# PineWoodDerby_Mega_Shield.net
KiCad netlist of a schematic drawn in EAGLE
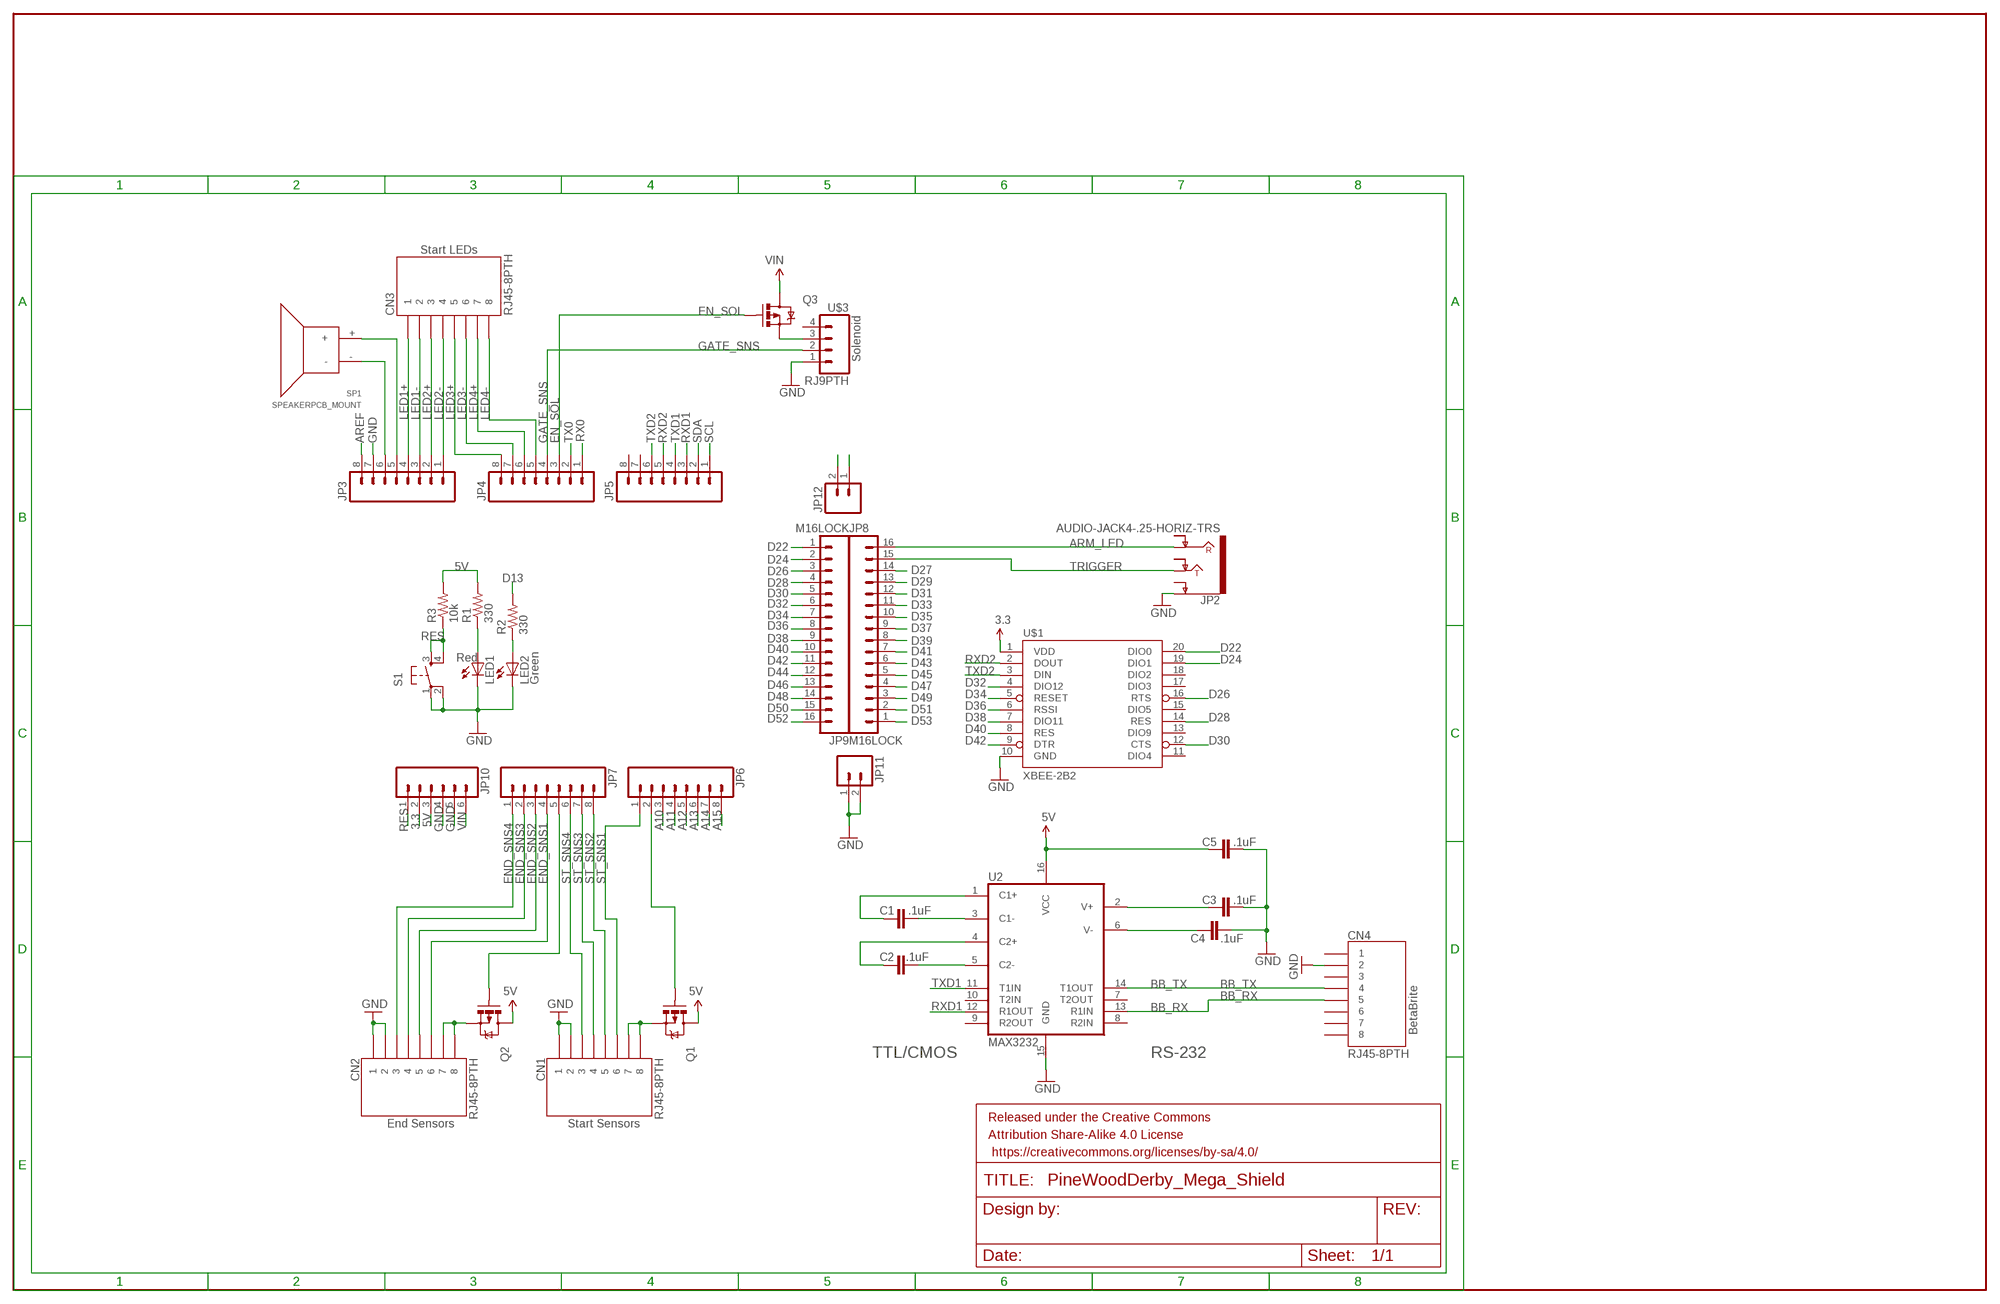
[diagram p0: schematic, sheet 1]

(export (version "E")
  (design (tool "Eeschema 10.0.6"))
  (components
    (comp (ref "C1")
      (value ".1uF")
      (footprint "eagle-import:0402-CAP")
      (libsource (lib "eagle-import") (part "CAP0402-CAP"))
    )
    (comp (ref "C2")
      (value ".1uF")
      (footprint "eagle-import:0402-CAP")
      (libsource (lib "eagle-import") (part "CAP0402-CAP"))
    )
    (comp (ref "C3")
      (value ".1uF")
      (footprint "eagle-import:0402-CAP")
      (libsource (lib "eagle-import") (part "CAP0402-CAP"))
    )
    (comp (ref "C4")
      (value ".1uF")
      (footprint "eagle-import:0402-CAP")
      (libsource (lib "eagle-import") (part "CAP0402-CAP"))
    )
    (comp (ref "C5")
      (value ".1uF")
      (footprint "eagle-import:0402-CAP")
      (libsource (lib "eagle-import") (part "CAP0402-CAP"))
    )
    (comp (ref "CN1")
      (value "RJ45-8PTH")
      (footprint "eagle-import:RJ45-8")
      (fields (field (name "LABEL") "Start Sensors"))
      (libsource (lib "eagle-import") (part "RJ45-8PTH"))
    )
    (comp (ref "CN2")
      (value "RJ45-8PTH")
      (footprint "eagle-import:RJ45-8")
      (fields (field (name "LABEL") "End Sensors"))
      (libsource (lib "eagle-import") (part "RJ45-8PTH"))
    )
    (comp (ref "CN3")
      (value "RJ45-8PTH")
      (footprint "eagle-import:RJ45-8")
      (fields (field (name "LABEL") "Start LEDs"))
      (libsource (lib "eagle-import") (part "RJ45-8PTH"))
    )
    (comp (ref "CN4")
      (value "RJ45-8PTH")
      (footprint "eagle-import:RJ45-8")
      (fields (field (name "LABEL") "BetaBrite"))
      (libsource (lib "eagle-import") (part "RJ45-8PTH"))
    )
    (comp (ref "FRAME2")
      (value "FRAME-LEDGER")
      (footprint "eagle-import:CREATIVE_COMMONS")
      (libsource (lib "eagle-import") (part "FRAME-LEDGER"))
    )
    (comp (ref "JP2")
      (value "AUDIO-JACK4-.25-HORIZ-TRS")
      (footprint "eagle-import:AUDIO-JACK-.25-INCH-HORIZ-PTH")
      (libsource (lib "eagle-import") (part "AUDIO-JACK4-.25-HORIZ-TRS"))
    )
    (comp (ref "JP3")
      (value "M08LOCK")
      (footprint "eagle-import:1X08_LOCK")
      (libsource (lib "eagle-import") (part "M08LOCK"))
    )
    (comp (ref "JP4")
      (value "M08LOCK")
      (footprint "eagle-import:1X08_LOCK")
      (libsource (lib "eagle-import") (part "M08LOCK"))
    )
    (comp (ref "JP5")
      (value "M08LOCK")
      (footprint "eagle-import:1X08_LOCK")
      (libsource (lib "eagle-import") (part "M08LOCK"))
    )
    (comp (ref "JP6")
      (value "M08LOCK")
      (footprint "eagle-import:1X08_LOCK")
      (libsource (lib "eagle-import") (part "M08LOCK"))
    )
    (comp (ref "JP7")
      (value "M08LOCK")
      (footprint "eagle-import:1X08_LOCK")
      (libsource (lib "eagle-import") (part "M08LOCK"))
    )
    (comp (ref "JP8")
      (value "M16LOCK")
      (footprint "eagle-import:1X16_LOCK")
      (libsource (lib "eagle-import") (part "M16LOCK"))
    )
    (comp (ref "JP9")
      (value "M16LOCK")
      (footprint "eagle-import:1X16_LOCK")
      (libsource (lib "eagle-import") (part "M16LOCK"))
    )
    (comp (ref "JP10")
      (value "M06LOCK")
      (footprint "eagle-import:1X06_LOCK")
      (libsource (lib "eagle-import") (part "M06LOCK"))
    )
    (comp (ref "JP11")
      (value "M02LOCK")
      (footprint "eagle-import:1X02_LOCK")
      (libsource (lib "eagle-import") (part "M02LOCK"))
    )
    (comp (ref "JP12")
      (value "M02LOCK")
      (footprint "eagle-import:1X02_LOCK")
      (libsource (lib "eagle-import") (part "M02LOCK"))
    )
    (comp (ref "LED1")
      (value "Red")
      (footprint "eagle-import:LED5MM")
      (libsource (lib "eagle-import") (part "LED5MM"))
    )
    (comp (ref "LED2")
      (value "Green")
      (footprint "eagle-import:LED5MM")
      (libsource (lib "eagle-import") (part "LED5MM"))
    )
    (comp (ref "Q1")
      (value "MOSFET-PCHANNELFQP27P06")
      (footprint "eagle-import:TO220V")
      (libsource (lib "eagle-import") (part "MOSFET-PCHANNELFQP27P06"))
    )
    (comp (ref "Q2")
      (value "MOSFET-PCHANNELFQP27P06")
      (footprint "eagle-import:TO220V")
      (libsource (lib "eagle-import") (part "MOSFET-PCHANNELFQP27P06"))
    )
    (comp (ref "Q3")
      (value "MOSFET-PCHANNELFQP27P06")
      (footprint "eagle-import:TO220V")
      (libsource (lib "eagle-import") (part "MOSFET-PCHANNELFQP27P06"))
    )
    (comp (ref "R1")
      (value "330")
      (footprint "eagle-import:AXIAL-0.3")
      (libsource (lib "eagle-import") (part "RESISTORPTH1"))
    )
    (comp (ref "R2")
      (value "330")
      (footprint "eagle-import:AXIAL-0.3")
      (libsource (lib "eagle-import") (part "RESISTORPTH1"))
    )
    (comp (ref "R3")
      (value "10k")
      (footprint "eagle-import:AXIAL-0.3")
      (libsource (lib "eagle-import") (part "RESISTORPTH1"))
    )
    (comp (ref "S1")
      (value "TAC_SWITCHPTH")
      (footprint "eagle-import:TACTILE-PTH")
      (libsource (lib "eagle-import") (part "TAC_SWITCHPTH"))
    )
    (comp (ref "SP1")
      (value "SPEAKERPCB_MOUNT")
      (footprint "eagle-import:PCB_MOUNT_SPEAKER")
      (fields (field (name "MFG") "SANCO"))
      (libsource (lib "eagle-import") (part "SPEAKERPCB_MOUNT"))
    )
    (comp (ref "U$1")
      (value "XBEE-2B2")
      (footprint "eagle-import:XBEE-SILK")
      (libsource (lib "eagle-import") (part "XBEE-2B2"))
    )
    (comp (ref "U$3")
      (value "RJ9PTH")
      (footprint "eagle-import:RJ9")
      (fields (field (name "LABEL") "Solenoid"))
      (libsource (lib "eagle-import") (part "RJ9PTH"))
    )
    (comp (ref "U2")
      (value "MAX3232")
      (footprint "eagle-import:SO016")
      (fields (field (name "PROD_ID") "IC-08171"))
      (libsource (lib "eagle-import") (part "MAX232SOIC16"))
    )
  )
  (nets
    (net (code "1") (name "/5V@1") (class "Default")
      (node (ref "JP12") (pin "1") (pinfunction "1_1") (pintype "passive"))
      (node (ref "JP12") (pin "2") (pinfunction "2_2") (pintype "passive"))
    )
    (net (code "2") (name "/A10") (class "Default")
      (node (ref "JP6") (pin "3") (pinfunction "3_3") (pintype "passive"))
    )
    (net (code "3") (name "/A11") (class "Default")
      (node (ref "JP6") (pin "4") (pinfunction "4_4") (pintype "passive"))
    )
    (net (code "4") (name "/A12") (class "Default")
      (node (ref "JP6") (pin "5") (pinfunction "5_5") (pintype "passive"))
    )
    (net (code "5") (name "/A13") (class "Default")
      (node (ref "JP6") (pin "6") (pinfunction "6_6") (pintype "passive"))
    )
    (net (code "6") (name "/A14") (class "Default")
      (node (ref "JP6") (pin "7") (pinfunction "7_7") (pintype "passive"))
    )
    (net (code "7") (name "/A15") (class "Default")
      (node (ref "JP6") (pin "8") (pinfunction "8_8") (pintype "passive"))
    )
    (net (code "8") (name "/AREF") (class "Default")
      (node (ref "JP3") (pin "8") (pinfunction "8_8") (pintype "passive"))
    )
    (net (code "9") (name "/ARM_LED") (class "Default")
      (node (ref "JP2") (pin "RING") (pinfunction "RING_RING") (pintype "bidirectional"))
      (node (ref "JP8") (pin "16") (pinfunction "16_16") (pintype "passive"))
    )
    (net (code "10") (name "/BB_RX") (class "Default")
      (node (ref "CN4") (pin "5") (pinfunction "5_5") (pintype "bidirectional"))
      (node (ref "U2") (pin "13") (pinfunction "R1IN_13") (pintype "input"))
    )
    (net (code "11") (name "/BB_TX") (class "Default")
      (node (ref "CN4") (pin "4") (pinfunction "4_4") (pintype "bidirectional"))
      (node (ref "U2") (pin "14") (pinfunction "T1OUT_14") (pintype "output"))
    )
    (net (code "12") (name "/D13") (class "Default")
      (node (ref "R2") (pin "P$2") (pinfunction "2_P$2") (pintype "passive"))
    )
    (net (code "13") (name "/D22") (class "Default")
      (node (ref "JP9") (pin "1") (pinfunction "1_1") (pintype "passive"))
      (node (ref "U$1") (pin "20") (pinfunction "DIO0_20") (pintype "bidirectional"))
    )
    (net (code "14") (name "/D24") (class "Default")
      (node (ref "JP9") (pin "2") (pinfunction "2_2") (pintype "passive"))
      (node (ref "U$1") (pin "19") (pinfunction "DIO1_19") (pintype "bidirectional"))
    )
    (net (code "15") (name "/D26") (class "Default")
      (node (ref "JP9") (pin "3") (pinfunction "3_3") (pintype "passive"))
      (node (ref "U$1") (pin "16") (pinfunction "RTS_16") (pintype "input"))
    )
    (net (code "16") (name "/D27") (class "Default")
      (node (ref "JP8") (pin "14") (pinfunction "14_14") (pintype "passive"))
    )
    (net (code "17") (name "/D28") (class "Default")
      (node (ref "JP9") (pin "4") (pinfunction "4_4") (pintype "passive"))
      (node (ref "U$1") (pin "14") (pinfunction "RES_14") (pintype "bidirectional"))
    )
    (net (code "18") (name "/D29") (class "Default")
      (node (ref "JP8") (pin "13") (pinfunction "13_13") (pintype "passive"))
    )
    (net (code "19") (name "/D30") (class "Default")
      (node (ref "JP9") (pin "5") (pinfunction "5_5") (pintype "passive"))
      (node (ref "U$1") (pin "12") (pinfunction "CTS_12") (pintype "output"))
    )
    (net (code "20") (name "/D31") (class "Default")
      (node (ref "JP8") (pin "12") (pinfunction "12_12") (pintype "passive"))
    )
    (net (code "21") (name "/D32") (class "Default")
      (node (ref "JP9") (pin "6") (pinfunction "6_6") (pintype "passive"))
      (node (ref "U$1") (pin "4") (pinfunction "DIO12_4") (pintype "bidirectional"))
    )
    (net (code "22") (name "/D33") (class "Default")
      (node (ref "JP8") (pin "11") (pinfunction "11_11") (pintype "passive"))
    )
    (net (code "23") (name "/D34") (class "Default")
      (node (ref "JP9") (pin "7") (pinfunction "7_7") (pintype "passive"))
      (node (ref "U$1") (pin "5") (pinfunction "RESET_5") (pintype "input"))
    )
    (net (code "24") (name "/D35") (class "Default")
      (node (ref "JP8") (pin "10") (pinfunction "10_10") (pintype "passive"))
    )
    (net (code "25") (name "/D36") (class "Default")
      (node (ref "JP9") (pin "8") (pinfunction "8_8") (pintype "passive"))
      (node (ref "U$1") (pin "6") (pinfunction "RSSI_6") (pintype "bidirectional"))
    )
    (net (code "26") (name "/D37") (class "Default")
      (node (ref "JP8") (pin "9") (pinfunction "9_9") (pintype "passive"))
    )
    (net (code "27") (name "/D38") (class "Default")
      (node (ref "JP9") (pin "9") (pinfunction "9_9") (pintype "passive"))
      (node (ref "U$1") (pin "7") (pinfunction "DIO11_7") (pintype "bidirectional"))
    )
    (net (code "28") (name "/D39") (class "Default")
      (node (ref "JP8") (pin "8") (pinfunction "8_8") (pintype "passive"))
    )
    (net (code "29") (name "/D40") (class "Default")
      (node (ref "JP9") (pin "10") (pinfunction "10_10") (pintype "passive"))
      (node (ref "U$1") (pin "8") (pinfunction "RES_8") (pintype "bidirectional"))
    )
    (net (code "30") (name "/D41") (class "Default")
      (node (ref "JP8") (pin "7") (pinfunction "7_7") (pintype "passive"))
    )
    (net (code "31") (name "/D42") (class "Default")
      (node (ref "JP9") (pin "11") (pinfunction "11_11") (pintype "passive"))
      (node (ref "U$1") (pin "9") (pinfunction "DTR_9") (pintype "bidirectional"))
    )
    (net (code "32") (name "/D43") (class "Default")
      (node (ref "JP8") (pin "6") (pinfunction "6_6") (pintype "passive"))
    )
    (net (code "33") (name "/D44") (class "Default")
      (node (ref "JP9") (pin "12") (pinfunction "12_12") (pintype "passive"))
    )
    (net (code "34") (name "/D45") (class "Default")
      (node (ref "JP8") (pin "5") (pinfunction "5_5") (pintype "passive"))
    )
    (net (code "35") (name "/D46") (class "Default")
      (node (ref "JP9") (pin "13") (pinfunction "13_13") (pintype "passive"))
    )
    (net (code "36") (name "/D47") (class "Default")
      (node (ref "JP8") (pin "4") (pinfunction "4_4") (pintype "passive"))
    )
    (net (code "37") (name "/D48") (class "Default")
      (node (ref "JP9") (pin "14") (pinfunction "14_14") (pintype "passive"))
    )
    (net (code "38") (name "/D49") (class "Default")
      (node (ref "JP8") (pin "3") (pinfunction "3_3") (pintype "passive"))
    )
    (net (code "39") (name "/D50") (class "Default")
      (node (ref "JP9") (pin "15") (pinfunction "15_15") (pintype "passive"))
    )
    (net (code "40") (name "/D51") (class "Default")
      (node (ref "JP8") (pin "2") (pinfunction "2_2") (pintype "passive"))
    )
    (net (code "41") (name "/D52") (class "Default")
      (node (ref "JP9") (pin "16") (pinfunction "16_16") (pintype "passive"))
    )
    (net (code "42") (name "/D53") (class "Default")
      (node (ref "JP8") (pin "1") (pinfunction "1_1") (pintype "passive"))
    )
    (net (code "43") (name "/END_SNS1") (class "Default")
      (node (ref "CN2") (pin "6") (pinfunction "6_6") (pintype "bidirectional"))
      (node (ref "JP7") (pin "4") (pinfunction "4_4") (pintype "passive"))
    )
    (net (code "44") (name "/END_SNS2") (class "Default")
      (node (ref "CN2") (pin "5") (pinfunction "5_5") (pintype "bidirectional"))
      (node (ref "JP7") (pin "3") (pinfunction "3_3") (pintype "passive"))
    )
    (net (code "45") (name "/END_SNS3") (class "Default")
      (node (ref "CN2") (pin "4") (pinfunction "4_4") (pintype "bidirectional"))
      (node (ref "JP7") (pin "2") (pinfunction "2_2") (pintype "passive"))
    )
    (net (code "46") (name "/END_SNS4") (class "Default")
      (node (ref "CN2") (pin "3") (pinfunction "3_3") (pintype "bidirectional"))
      (node (ref "JP7") (pin "1") (pinfunction "1_1") (pintype "passive"))
    )
    (net (code "47") (name "/EN_SOL") (class "Default")
      (node (ref "JP4") (pin "3") (pinfunction "3_3") (pintype "passive"))
      (node (ref "Q3") (pin "1") (pinfunction "G_1") (pintype "passive"))
    )
    (net (code "48") (name "/GATE_SNS") (class "Default")
      (node (ref "JP4") (pin "4") (pinfunction "4_4") (pintype "passive"))
      (node (ref "U$3") (pin "2") (pinfunction "2_2") (pintype "passive"))
    )
    (net (code "49") (name "/LED1+") (class "Default")
      (node (ref "CN3") (pin "1") (pinfunction "1_1") (pintype "bidirectional"))
      (node (ref "JP3") (pin "4") (pinfunction "4_4") (pintype "passive"))
    )
    (net (code "50") (name "/LED1-") (class "Default")
      (node (ref "CN3") (pin "2") (pinfunction "2_2") (pintype "bidirectional"))
      (node (ref "JP3") (pin "3") (pinfunction "3_3") (pintype "passive"))
    )
    (net (code "51") (name "/LED2+") (class "Default")
      (node (ref "CN3") (pin "3") (pinfunction "3_3") (pintype "bidirectional"))
      (node (ref "JP3") (pin "2") (pinfunction "2_2") (pintype "passive"))
    )
    (net (code "52") (name "/LED2-") (class "Default")
      (node (ref "CN3") (pin "4") (pinfunction "4_4") (pintype "bidirectional"))
      (node (ref "JP3") (pin "1") (pinfunction "1_1") (pintype "passive"))
    )
    (net (code "53") (name "/LED3+") (class "Default")
      (node (ref "CN3") (pin "5") (pinfunction "5_5") (pintype "bidirectional"))
      (node (ref "JP4") (pin "8") (pinfunction "8_8") (pintype "passive"))
    )
    (net (code "54") (name "/LED3-") (class "Default")
      (node (ref "CN3") (pin "6") (pinfunction "6_6") (pintype "bidirectional"))
      (node (ref "JP4") (pin "7") (pinfunction "7_7") (pintype "passive"))
    )
    (net (code "55") (name "/LED4+") (class "Default")
      (node (ref "CN3") (pin "7") (pinfunction "7_7") (pintype "bidirectional"))
      (node (ref "JP4") (pin "6") (pinfunction "6_6") (pintype "passive"))
    )
    (net (code "56") (name "/LED4-") (class "Default")
      (node (ref "CN3") (pin "8") (pinfunction "8_8") (pintype "bidirectional"))
      (node (ref "JP4") (pin "5") (pinfunction "5_5") (pintype "passive"))
    )
    (net (code "57") (name "/RES") (class "Default")
      (node (ref "JP10") (pin "1") (pinfunction "1_1") (pintype "passive"))
      (node (ref "R3") (pin "P$1") (pinfunction "1_P$1") (pintype "passive"))
      (node (ref "S1") (pin "3") (pinfunction "3_3") (pintype "passive"))
      (node (ref "S1") (pin "4") (pinfunction "4_4") (pintype "passive"))
    )
    (net (code "58") (name "/RX0") (class "Default")
      (node (ref "JP4") (pin "1") (pinfunction "1_1") (pintype "passive"))
    )
    (net (code "59") (name "/RXD1") (class "Default")
      (node (ref "JP5") (pin "3") (pinfunction "3_3") (pintype "passive"))
      (node (ref "U2") (pin "12") (pinfunction "R1OUT_12") (pintype "output"))
    )
    (net (code "60") (name "/RXD2") (class "Default")
      (node (ref "JP5") (pin "5") (pinfunction "5_5") (pintype "passive"))
      (node (ref "U$1") (pin "2") (pinfunction "DOUT_2") (pintype "output"))
    )
    (net (code "61") (name "/SCL") (class "Default")
      (node (ref "JP5") (pin "1") (pinfunction "1_1") (pintype "passive"))
    )
    (net (code "62") (name "/SDA") (class "Default")
      (node (ref "JP5") (pin "2") (pinfunction "2_2") (pintype "passive"))
    )
    (net (code "63") (name "/ST_SNS1") (class "Default")
      (node (ref "CN1") (pin "6") (pinfunction "6_6") (pintype "bidirectional"))
      (node (ref "JP6") (pin "1") (pinfunction "1_1") (pintype "passive"))
    )
    (net (code "64") (name "/ST_SNS2") (class "Default")
      (node (ref "CN1") (pin "5") (pinfunction "5_5") (pintype "bidirectional"))
      (node (ref "JP7") (pin "8") (pinfunction "8_8") (pintype "passive"))
    )
    (net (code "65") (name "/ST_SNS3") (class "Default")
      (node (ref "CN1") (pin "4") (pinfunction "4_4") (pintype "bidirectional"))
      (node (ref "JP7") (pin "7") (pinfunction "7_7") (pintype "passive"))
    )
    (net (code "66") (name "/ST_SNS4") (class "Default")
      (node (ref "CN1") (pin "3") (pinfunction "3_3") (pintype "bidirectional"))
      (node (ref "JP7") (pin "6") (pinfunction "6_6") (pintype "passive"))
    )
    (net (code "67") (name "/TRIGGER") (class "Default")
      (node (ref "JP2") (pin "TIP") (pinfunction "TIP_TIP") (pintype "bidirectional"))
      (node (ref "JP8") (pin "15") (pinfunction "15_15") (pintype "passive"))
    )
    (net (code "68") (name "/TX0") (class "Default")
      (node (ref "JP4") (pin "2") (pinfunction "2_2") (pintype "passive"))
    )
    (net (code "69") (name "/TXD1") (class "Default")
      (node (ref "JP5") (pin "4") (pinfunction "4_4") (pintype "passive"))
      (node (ref "U2") (pin "11") (pinfunction "T1IN_11") (pintype "input"))
    )
    (net (code "70") (name "/TXD2") (class "Default")
      (node (ref "JP5") (pin "6") (pinfunction "6_6") (pintype "passive"))
      (node (ref "U$1") (pin "3") (pinfunction "DIN_3") (pintype "input"))
    )
    (net (code "71") (name "3.3") (class "Default")
      (node (ref "JP10") (pin "2") (pinfunction "2_2") (pintype "passive"))
      (node (ref "U$1") (pin "1") (pinfunction "VDD_1") (pintype "power_in"))
    )
    (net (code "72") (name "5V") (class "Default")
      (node (ref "C5") (pin "1") (pinfunction "1_1") (pintype "passive"))
      (node (ref "JP10") (pin "3") (pinfunction "3_3") (pintype "passive"))
      (node (ref "Q1") (pin "2") (pinfunction "D_2") (pintype "passive"))
      (node (ref "Q2") (pin "2") (pinfunction "D_2") (pintype "passive"))
      (node (ref "R1") (pin "P$2") (pinfunction "2_P$2") (pintype "passive"))
      (node (ref "R3") (pin "P$2") (pinfunction "2_P$2") (pintype "passive"))
      (node (ref "U2") (pin "16") (pinfunction "VCC_16") (pintype "bidirectional"))
    )
    (net (code "73") (name "GND") (class "Default")
      (node (ref "C3") (pin "2") (pinfunction "2_2") (pintype "passive"))
      (node (ref "C4") (pin "2") (pinfunction "2_2") (pintype "passive"))
      (node (ref "C5") (pin "2") (pinfunction "2_2") (pintype "passive"))
      (node (ref "CN1") (pin "1") (pinfunction "1_1") (pintype "bidirectional"))
      (node (ref "CN1") (pin "2") (pinfunction "2_2") (pintype "bidirectional"))
      (node (ref "CN2") (pin "1") (pinfunction "1_1") (pintype "bidirectional"))
      (node (ref "CN2") (pin "2") (pinfunction "2_2") (pintype "bidirectional"))
      (node (ref "CN4") (pin "2") (pinfunction "2_2") (pintype "bidirectional"))
      (node (ref "JP10") (pin "4") (pinfunction "4_4") (pintype "passive"))
      (node (ref "JP10") (pin "5") (pinfunction "5_5") (pintype "passive"))
      (node (ref "JP11") (pin "1") (pinfunction "1_1") (pintype "passive"))
      (node (ref "JP11") (pin "2") (pinfunction "2_2") (pintype "passive"))
      (node (ref "JP2") (pin "SLEEVE") (pinfunction "EARTH_SLEEVE") (pintype "bidirectional"))
      (node (ref "JP3") (pin "7") (pinfunction "7_7") (pintype "passive"))
      (node (ref "LED1") (pin "K") (pinfunction "C_K") (pintype "passive"))
      (node (ref "LED2") (pin "K") (pinfunction "C_K") (pintype "passive"))
      (node (ref "S1") (pin "1") (pinfunction "1_1") (pintype "passive"))
      (node (ref "S1") (pin "2") (pinfunction "2_2") (pintype "passive"))
      (node (ref "U$1") (pin "10") (pinfunction "GND_10") (pintype "power_in"))
      (node (ref "U$3") (pin "1") (pinfunction "1_1") (pintype "passive"))
      (node (ref "U2") (pin "15") (pinfunction "GND_15") (pintype "bidirectional"))
    )
    (net (code "74") (name "Net-(JP3-Pad5)") (class "Default")
      (node (ref "JP3") (pin "5") (pinfunction "5_5") (pintype "passive"))
      (node (ref "SP1") (pin "+") (pinfunction "+_+") (pintype "bidirectional"))
    )
    (net (code "75") (name "Net-(JP3-Pad6)") (class "Default")
      (node (ref "JP3") (pin "6") (pinfunction "6_6") (pintype "passive"))
      (node (ref "SP1") (pin "-") (pinfunction "-_-") (pintype "bidirectional"))
    )
    (net (code "76") (name "Net-(Q1-G)") (class "Default")
      (node (ref "JP6") (pin "2") (pinfunction "2_2") (pintype "passive"))
      (node (ref "Q1") (pin "1") (pinfunction "G_1") (pintype "passive"))
    )
    (net (code "77") (name "Net-(Q1-S)") (class "Default")
      (node (ref "CN1") (pin "7") (pinfunction "7_7") (pintype "bidirectional"))
      (node (ref "CN1") (pin "8") (pinfunction "8_8") (pintype "bidirectional"))
      (node (ref "Q1") (pin "3") (pinfunction "S_3") (pintype "passive"))
    )
    (net (code "78") (name "Net-(Q2-G)") (class "Default")
      (node (ref "JP7") (pin "5") (pinfunction "5_5") (pintype "passive"))
      (node (ref "Q2") (pin "1") (pinfunction "G_1") (pintype "passive"))
    )
    (net (code "79") (name "Net-(Q2-S)") (class "Default")
      (node (ref "CN2") (pin "7") (pinfunction "7_7") (pintype "bidirectional"))
      (node (ref "CN2") (pin "8") (pinfunction "8_8") (pintype "bidirectional"))
      (node (ref "Q2") (pin "3") (pinfunction "S_3") (pintype "passive"))
    )
    (net (code "80") (name "Net-(Q3-S)") (class "Default")
      (node (ref "Q3") (pin "3") (pinfunction "S_3") (pintype "passive"))
      (node (ref "U$3") (pin "3") (pinfunction "3_3") (pintype "passive"))
    )
    (net (code "81") (name "Net-(R1-1)") (class "Default")
      (node (ref "LED1") (pin "A") (pinfunction "A_A") (pintype "passive"))
      (node (ref "R1") (pin "P$1") (pinfunction "1_P$1") (pintype "passive"))
    )
    (net (code "82") (name "Net-(R2-1)") (class "Default")
      (node (ref "LED2") (pin "A") (pinfunction "A_A") (pintype "passive"))
      (node (ref "R2") (pin "P$1") (pinfunction "1_P$1") (pintype "passive"))
    )
    (net (code "83") (name "Net-(U2-C1+)") (class "Default")
      (node (ref "C1") (pin "1") (pinfunction "1_1") (pintype "passive"))
      (node (ref "U2") (pin "1") (pinfunction "C1+_1") (pintype "bidirectional"))
    )
    (net (code "84") (name "Net-(U2-C1-)") (class "Default")
      (node (ref "C1") (pin "2") (pinfunction "2_2") (pintype "passive"))
      (node (ref "U2") (pin "3") (pinfunction "C1-_3") (pintype "bidirectional"))
    )
    (net (code "85") (name "Net-(U2-C2+)") (class "Default")
      (node (ref "C2") (pin "1") (pinfunction "1_1") (pintype "passive"))
      (node (ref "U2") (pin "4") (pinfunction "C2+_4") (pintype "bidirectional"))
    )
    (net (code "86") (name "Net-(U2-C2-)") (class "Default")
      (node (ref "C2") (pin "2") (pinfunction "2_2") (pintype "passive"))
      (node (ref "U2") (pin "5") (pinfunction "C2-_5") (pintype "bidirectional"))
    )
    (net (code "87") (name "Net-(U2-V+)") (class "Default")
      (node (ref "C3") (pin "1") (pinfunction "1_1") (pintype "passive"))
      (node (ref "U2") (pin "2") (pinfunction "V+_2") (pintype "bidirectional"))
    )
    (net (code "88") (name "Net-(U2-V-)") (class "Default")
      (node (ref "C4") (pin "1") (pinfunction "1_1") (pintype "passive"))
      (node (ref "U2") (pin "6") (pinfunction "V-_6") (pintype "bidirectional"))
    )
    (net (code "89") (name "VIN") (class "Default")
      (node (ref "JP10") (pin "6") (pinfunction "6_6") (pintype "passive"))
      (node (ref "Q3") (pin "2") (pinfunction "D_2") (pintype "passive"))
    )
    (net (code "90") (name "unconnected-(CN4-Pad1)") (class "Default")
      (node (ref "CN4") (pin "1") (pinfunction "1_1") (pintype "bidirectional"))
    )
    (net (code "91") (name "unconnected-(CN4-Pad3)") (class "Default")
      (node (ref "CN4") (pin "3") (pinfunction "3_3") (pintype "bidirectional"))
    )
    (net (code "92") (name "unconnected-(CN4-Pad6)") (class "Default")
      (node (ref "CN4") (pin "6") (pinfunction "6_6") (pintype "bidirectional"))
    )
    (net (code "93") (name "unconnected-(CN4-Pad7)") (class "Default")
      (node (ref "CN4") (pin "7") (pinfunction "7_7") (pintype "bidirectional"))
    )
    (net (code "94") (name "unconnected-(CN4-Pad8)") (class "Default")
      (node (ref "CN4") (pin "8") (pinfunction "8_8") (pintype "bidirectional"))
    )
    (net (code "95") (name "unconnected-(JP2-EARTH-NORM-PadSLEEVE-NORM)") (class "Default")
      (node (ref "JP2") (pin "SLEEVE-NORM") (pinfunction "EARTH-NORM_SLEEVE-NORM") (pintype "bidirectional"))
    )
    (net (code "96") (name "unconnected-(JP2-PadRING-NORM)") (class "Default")
      (node (ref "JP2") (pin "RING-NORM") (pinfunction "RING-NORM_RING-NORM") (pintype "bidirectional"))
    )
    (net (code "97") (name "unconnected-(JP2-PadTIP-NORM)") (class "Default")
      (node (ref "JP2") (pin "TIP-NORM") (pinfunction "TIP-NORM_TIP-NORM") (pintype "bidirectional"))
    )
    (net (code "98") (name "unconnected-(JP5-Pad7)") (class "Default")
      (node (ref "JP5") (pin "7") (pinfunction "7_7") (pintype "passive"))
    )
    (net (code "99") (name "unconnected-(JP5-Pad8)") (class "Default")
      (node (ref "JP5") (pin "8") (pinfunction "8_8") (pintype "passive"))
    )
    (net (code "100") (name "unconnected-(U$1-DIO2-Pad18)") (class "Default")
      (node (ref "U$1") (pin "18") (pinfunction "DIO2_18") (pintype "bidirectional"))
    )
    (net (code "101") (name "unconnected-(U$1-DIO3-Pad17)") (class "Default")
      (node (ref "U$1") (pin "17") (pinfunction "DIO3_17") (pintype "bidirectional"))
    )
    (net (code "102") (name "unconnected-(U$1-DIO4-Pad11)") (class "Default")
      (node (ref "U$1") (pin "11") (pinfunction "DIO4_11") (pintype "bidirectional"))
    )
    (net (code "103") (name "unconnected-(U$1-DIO5-Pad15)") (class "Default")
      (node (ref "U$1") (pin "15") (pinfunction "DIO5_15") (pintype "bidirectional"))
    )
    (net (code "104") (name "unconnected-(U$1-DIO9-Pad13)") (class "Default")
      (node (ref "U$1") (pin "13") (pinfunction "DIO9_13") (pintype "bidirectional"))
    )
    (net (code "105") (name "unconnected-(U$3-Pad4)") (class "Default")
      (node (ref "U$3") (pin "4") (pinfunction "4_4") (pintype "passive"))
    )
    (net (code "106") (name "unconnected-(U2-R2IN-Pad8)") (class "Default")
      (node (ref "U2") (pin "8") (pinfunction "R2IN_8") (pintype "input"))
    )
    (net (code "107") (name "unconnected-(U2-R2OUT-Pad9)") (class "Default")
      (node (ref "U2") (pin "9") (pinfunction "R2OUT_9") (pintype "output"))
    )
    (net (code "108") (name "unconnected-(U2-T2IN-Pad10)") (class "Default")
      (node (ref "U2") (pin "10") (pinfunction "T2IN_10") (pintype "input"))
    )
    (net (code "109") (name "unconnected-(U2-T2OUT-Pad7)") (class "Default")
      (node (ref "U2") (pin "7") (pinfunction "T2OUT_7") (pintype "output"))
    )
  )
)
